# single_coil_driver.net
KiCad netlist of a schematic drawn in Altium Designer
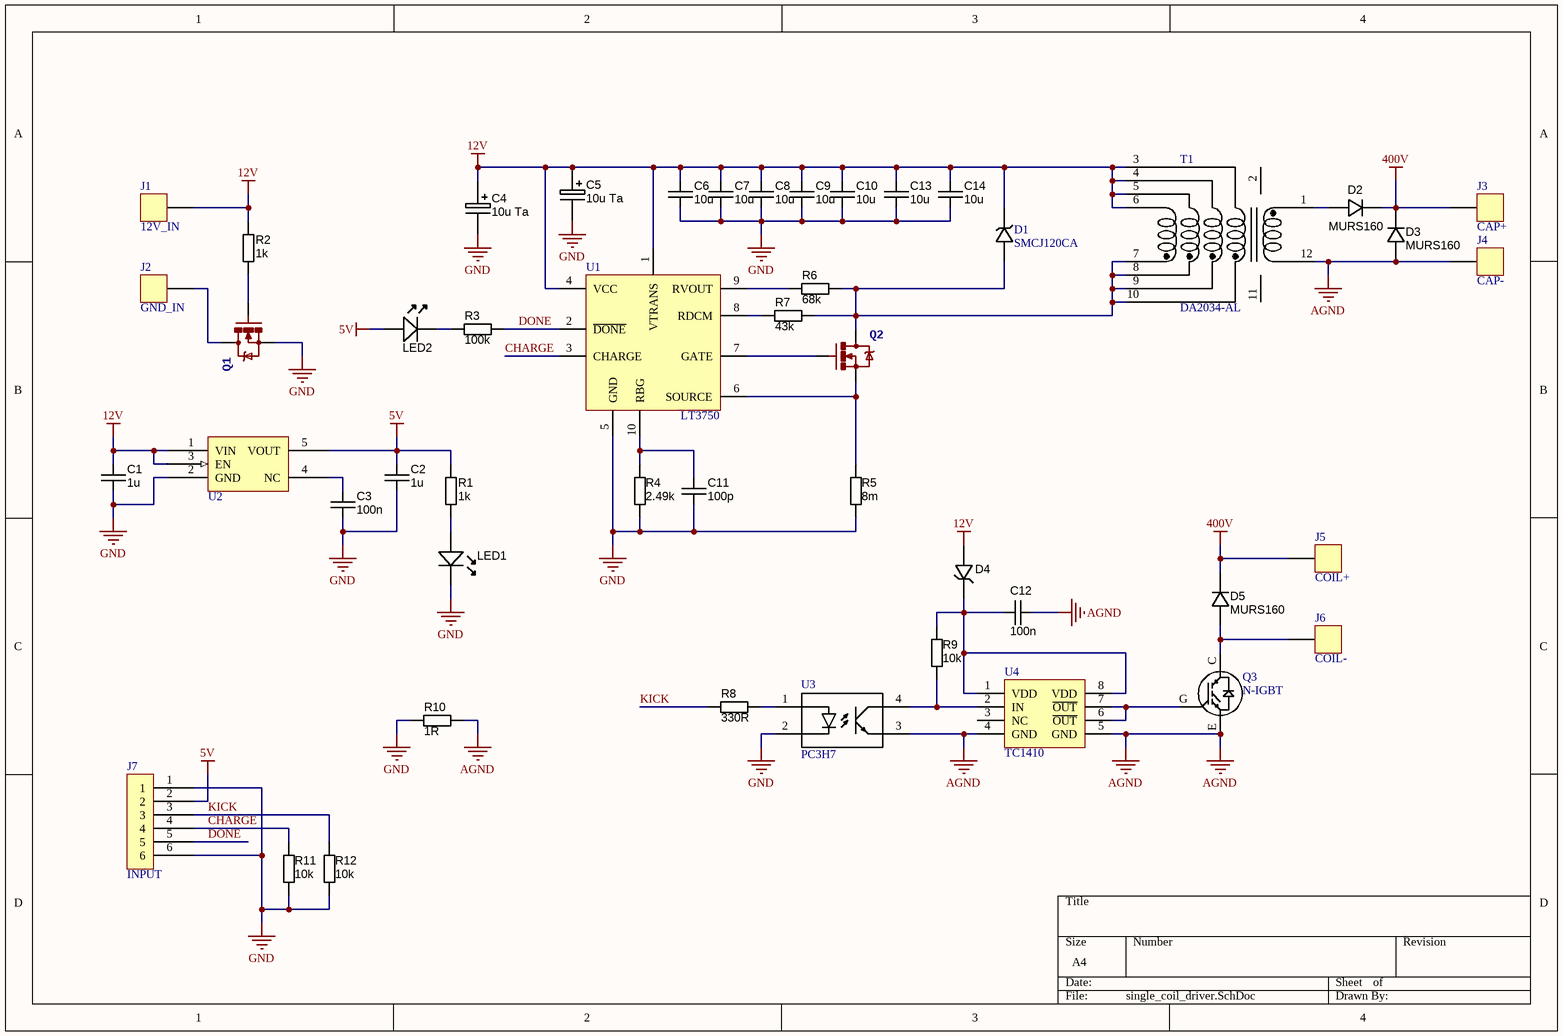
[diagram p0: single_coil_driver.SchDoc]

(export (version "E")
  (design (tool "Eeschema 10.0.6"))
  (components
    (comp (ref "C1")
      (value "1u")
      (footprint "CAPC3216X180N")
      (description "Capacitor SMD Cer 10uF 10% 16V X7R 1206")
      (fields (field (name "TOLERANCE") "±10%"))
      (libsource (lib "PBL - Capacitors") (part "CAPC_10u_1206_16V"))
    )
    (comp (ref "C2")
      (value "1u")
      (footprint "CAPC3216X180N")
      (description "Capacitor SMD Cer 10uF 10% 16V X7R 1206")
      (fields (field (name "TOLERANCE") "±10%"))
      (libsource (lib "PBL - Capacitors") (part "CAPC_10u_1206_16V"))
    )
    (comp (ref "C3")
      (value "100n")
      (footprint "CAPC1608X90N")
      (description "Capacitor SMD Cer 10nF 10% 50V X7R 0603")
      (fields (field (name "TOLERANCE") "±10%"))
      (libsource (lib "PBL - Capacitors") (part "CAPC_10n_0603_X7R_50V_10%"))
    )
    (comp (ref "C4")
      (value "10u Ta")
      (footprint "CAPMP3528X210N")
      (description "Capacitor SMD Tantalum 47uF 20% 6.3V 1210")
      (fields (field (name "TOLERANCE") "±20%"))
      (libsource (lib "PBL - Capacitors") (part "CAPT_47u_1210_6V3"))
    )
    (comp (ref "C5")
      (value "10u Ta")
      (footprint "CAPMP3528X210N")
      (description "Capacitor SMD Tantalum 47uF 20% 6.3V 1210")
      (fields (field (name "TOLERANCE") "±20%"))
      (libsource (lib "PBL - Capacitors") (part "CAPT_47u_1210_6V3"))
    )
    (comp (ref "C6")
      (value "10u")
      (footprint "CAPC3216X180N")
      (description "Capacitor SMD Cer 10uF 10% 16V X7R 1206")
      (fields (field (name "TOLERANCE") "±10%"))
      (libsource (lib "PBL - Capacitors") (part "CAPC_10u_1206_16V"))
    )
    (comp (ref "C7")
      (value "10u")
      (footprint "CAPC3216X180N")
      (description "Capacitor SMD Cer 10uF 10% 16V X7R 1206")
      (fields (field (name "TOLERANCE") "±10%"))
      (libsource (lib "PBL - Capacitors") (part "CAPC_10u_1206_16V"))
    )
    (comp (ref "C8")
      (value "10u")
      (footprint "CAPC3216X180N")
      (description "Capacitor SMD Cer 10uF 10% 16V X7R 1206")
      (fields (field (name "TOLERANCE") "±10%"))
      (libsource (lib "PBL - Capacitors") (part "CAPC_10u_1206_16V"))
    )
    (comp (ref "C9")
      (value "10u")
      (footprint "CAPC3216X180N")
      (description "Capacitor SMD Cer 10uF 10% 16V X7R 1206")
      (fields (field (name "TOLERANCE") "±10%"))
      (libsource (lib "PBL - Capacitors") (part "CAPC_10u_1206_16V"))
    )
    (comp (ref "C10")
      (value "10u")
      (footprint "CAPC3216X180N")
      (description "Capacitor SMD Cer 10uF 10% 16V X7R 1206")
      (fields (field (name "TOLERANCE") "±10%"))
      (libsource (lib "PBL - Capacitors") (part "CAPC_10u_1206_16V"))
    )
    (comp (ref "C11")
      (value "100p")
      (footprint "CAPC1608X90N")
      (description "Capacitor SMD Cer 10nF 10% 50V X7R 0603")
      (fields (field (name "TOLERANCE") "±10%"))
      (libsource (lib "PBL - Capacitors") (part "CAPC_10n_0603_X7R_50V_10%"))
    )
    (comp (ref "C12")
      (value "100n")
      (footprint "CAPC1608X90N")
      (description "Capacitor SMD Cer 10nF 10% 50V X7R 0603")
      (fields (field (name "TOLERANCE") "±10%"))
      (libsource (lib "PBL - Capacitors") (part "CAPC_10n_0603_X7R_50V_10%"))
    )
    (comp (ref "C13")
      (value "10u")
      (footprint "CAPC3216X180N")
      (description "Capacitor SMD Cer 10uF 10% 16V X7R 1206")
      (fields (field (name "TOLERANCE") "±10%"))
      (libsource (lib "PBL - Capacitors") (part "CAPC_10u_1206_16V"))
    )
    (comp (ref "C14")
      (value "10u")
      (footprint "CAPC3216X180N")
      (description "Capacitor SMD Cer 10uF 10% 16V X7R 1206")
      (fields (field (name "TOLERANCE") "±10%"))
      (libsource (lib "PBL - Capacitors") (part "CAPC_10u_1206_16V"))
    )
    (comp (ref "D1")
      (value "SMCJ120CA")
      (footprint "DO-214AB")
      (libsource (lib "coilgun") (part "TVS-DIODE"))
    )
    (comp (ref "D2")
      (value "MURS160")
      (footprint "DO-214AA")
      (description "Diode SMD 100V 1.5A SMA")
      (libsource (lib "PBL - Diodes") (part "DIODE_100V_1.5A_SMA"))
    )
    (comp (ref "D3")
      (value "MURS160")
      (footprint "DO-214AA")
      (description "Diode SMD 100V 1.5A SMA")
      (libsource (lib "PBL - Diodes") (part "DIODE_100V_1.5A_SMA"))
    )
    (comp (ref "D4")
      (value "~")
      (footprint "SOD123")
      (description "Diode Zener SMD 28V 0.5W SOD-123")
      (fields (field (name "TOLERANCE") "±5%"))
      (libsource (lib "PBL - Diodes") (part "DIODE_ZENER_28V_500mW"))
    )
    (comp (ref "D5")
      (value "MURS160")
      (footprint "DO-214AA")
      (description "Diode SMD 100V 1.5A SMA")
      (libsource (lib "PBL - Diodes") (part "DIODE_100V_1.5A_SMA"))
    )
    (comp (ref "J1") (value "12V_IN") (footprint "MEDIUM-POWER-VIA") (libsource (lib "") (part "HEADER-1_1")))
    (comp (ref "J2") (value "GND_IN") (footprint "MEDIUM-POWER-VIA") (libsource (lib "") (part "HEADER-1_1")))
    (comp (ref "J3")
      (value "CAP+")
      (footprint "MEDIUM-POWER-VIA")
      (libsource (lib "connectors") (part "HEADER-1"))
    )
    (comp (ref "J4")
      (value "CAP-")
      (footprint "MEDIUM-POWER-VIA")
      (libsource (lib "connectors") (part "HEADER-1"))
    )
    (comp (ref "J5")
      (value "COIL+")
      (footprint "MEDIUM-POWER-VIA")
      (libsource (lib "connectors") (part "HEADER-1"))
    )
    (comp (ref "J6")
      (value "COIL-")
      (footprint "MEDIUM-POWER-VIA")
      (libsource (lib "connectors") (part "HEADER-1"))
    )
    (comp (ref "J7")
      (value "INPUT")
      (footprint "MICRO-MATCH-6")
      (libsource (lib "connectors") (part "HEADER-6"))
    )
    (comp (ref "LED1")
      (value "Green")
      (footprint "LED-0603-GREEN")
      (description "LED 0603 SMD Green 525nm 350mcd 20mA")
      (libsource (lib "PBL - Light Sources") (part "LED_SMD_Green_0603_525nm_350mcd"))
    )
    (comp (ref "LED2")
      (value "Green")
      (footprint "LED-0603-GREEN")
      (description "LED 0603 SMD Green 525nm 350mcd 20mA")
      (libsource (lib "PBL - Light Sources") (part "LED_SMD_Green_0603_525nm_350mcd"))
    )
    (comp (ref "Q1") (value "MOSFET-N") (footprint "SOT669") (libsource (lib "") (part "MOSFET-N_1")))
    (comp (ref "Q2") (value "MOSFET-N") (footprint "SOT669") (libsource (lib "mosfets") (part "MOSFET-N")))
    (comp (ref "Q3") (value "N-IGBT") (footprint "TO-247") (libsource (lib "coilgun") (part "N-IGBT")))
    (comp (ref "R1")
      (value "1k")
      (footprint "RESC1608X55N")
      (description "Resistor SMD chip 1k Ohm 0.1W 1% 0603")
      (fields (field (name "TOLERANCE") "±1%"))
      (libsource (lib "PBL - Resistors") (part "RES_1K_0603_1%"))
    )
    (comp (ref "R2")
      (value "1k")
      (footprint "RESC1608X55N")
      (description "Resistor SMD chip 1k Ohm 0.1W 1% 0603")
      (fields (field (name "TOLERANCE") "±1%"))
      (libsource (lib "PBL - Resistors") (part "RES_1K_0603_1%"))
    )
    (comp (ref "R3")
      (value "100k")
      (footprint "RESC1608X55N")
      (description "Resistor SMD chip 1k Ohm 0.1W 1% 0603")
      (fields (field (name "TOLERANCE") "±1%"))
      (libsource (lib "") (part "RES_1K_0603_1%_1"))
    )
    (comp (ref "R4")
      (value "2.49k")
      (footprint "RESC1608X55N")
      (description "Resistor SMD chip 1k Ohm 0.1W 1% 0603")
      (fields (field (name "TOLERANCE") "±1%"))
      (libsource (lib "") (part "RES_1K_0603_1%_2"))
    )
    (comp (ref "R5")
      (value "8m")
      (footprint "RESC5025X70N")
      (description "Resistor SMD chip 10 Ohm 0.25W 5% 2010")
      (fields (field (name "TOLERANCE") "±5%"))
      (libsource (lib "PBL - Resistors") (part "RES_10R_2010_5%"))
    )
    (comp (ref "R6")
      (value "68k")
      (footprint "RESC1608X55N")
      (description "Resistor SMD chip 1k Ohm 0.1W 1% 0603")
      (fields (field (name "TOLERANCE") "±1%"))
      (libsource (lib "") (part "RES_1K_0603_1%_3"))
    )
    (comp (ref "R7")
      (value "43k")
      (footprint "RESC1608X55N")
      (description "Resistor SMD chip 1k Ohm 0.1W 1% 0603")
      (fields (field (name "TOLERANCE") "±1%"))
      (libsource (lib "") (part "RES_1K_0603_1%_3"))
    )
    (comp (ref "R8")
      (value "330R")
      (footprint "RESC1608X55N")
      (description "Resistor SMD chip 1k Ohm 0.1W 1% 0603")
      (fields (field (name "TOLERANCE") "±1%"))
      (libsource (lib "") (part "RES_1K_0603_1%_1"))
    )
    (comp (ref "R9")
      (value "10k")
      (footprint "RESC1608X55N")
      (description "Resistor SMD chip 1k Ohm 0.1W 1% 0603")
      (fields (field (name "TOLERANCE") "±1%"))
      (libsource (lib "PBL - Resistors") (part "RES_1K_0603_1%"))
    )
    (comp (ref "R10")
      (value "1R")
      (footprint "RESC1608X55N")
      (description "Resistor SMD chip 1k Ohm 0.1W 1% 0603")
      (fields (field (name "TOLERANCE") "±1%"))
      (libsource (lib "") (part "RES_1K_0603_1%_1"))
    )
    (comp (ref "R11")
      (value "10k")
      (footprint "RESC1608X55N")
      (description "Resistor SMD chip 1k Ohm 0.1W 1% 0603")
      (fields (field (name "TOLERANCE") "±1%"))
      (libsource (lib "PBL - Resistors") (part "RES_1K_0603_1%"))
    )
    (comp (ref "R12")
      (value "10k")
      (footprint "RESC1608X55N")
      (description "Resistor SMD chip 1k Ohm 0.1W 1% 0603")
      (fields (field (name "TOLERANCE") "±1%"))
      (libsource (lib "PBL - Resistors") (part "RES_1K_0603_1%"))
    )
    (comp (ref "T1")
      (value "DA2034-AL")
      (footprint "DA2034-AL")
      (libsource (lib "coilgun") (part "DA2034-AL"))
    )
    (comp (ref "U1") (value "LT3750") (footprint "MSOP-10") (libsource (lib "coilgun") (part "LT3750")))
    (comp (ref "U2")
      (value "LDO-SOT23-5")
      (footprint "SOT23-5")
      (libsource (lib "power") (part "LDO-SOT23-5"))
    )
    (comp (ref "U3")
      (value "PC3H7")
      (footprint "SOIC127P680X230-4M")
      (libsource (lib "coilgun") (part "PC3H7"))
    )
    (comp (ref "U4") (value "TC1410") (footprint "SO8") (libsource (lib "coilgun") (part "TC1410")))
  )
  (nets
    (net (code "1") (name "/CHARGE") (class "Default")
      (node (ref "J7") (pin "4") (pinfunction "4_4") (pintype "passive"))
      (node (ref "R11") (pin "1") (pinfunction "1_1") (pintype "passive"))
      (node (ref "U1") (pin "3") (pinfunction "CHARGE_3") (pintype "passive"))
    )
    (net (code "2") (name "/DONE") (class "Default")
      (node (ref "J7") (pin "5") (pinfunction "5_5") (pintype "passive"))
      (node (ref "R3") (pin "1") (pinfunction "1_1") (pintype "passive"))
      (node (ref "U1") (pin "2") (pinfunction "~{DONE}_2") (pintype "passive"))
    )
    (net (code "3") (name "/KICK") (class "Default")
      (node (ref "J7") (pin "3") (pinfunction "3_3") (pintype "passive"))
      (node (ref "R12") (pin "1") (pinfunction "1_1") (pintype "passive"))
      (node (ref "R8") (pin "2") (pinfunction "2_2") (pintype "passive"))
    )
    (net (code "4") (name "5V") (class "Default")
      (node (ref "C2") (pin "1") (pintype "passive"))
      (node (ref "J7") (pin "2") (pinfunction "2_2") (pintype "passive"))
      (node (ref "LED2") (pin "A") (pinfunction "A_A") (pintype "passive"))
      (node (ref "R1") (pin "1") (pinfunction "1_1") (pintype "passive"))
      (node (ref "U2") (pin "5") (pinfunction "VOUT_5") (pintype "passive"))
    )
    (net (code "5") (name "12V") (class "Default")
      (node (ref "C1") (pin "1") (pintype "passive"))
      (node (ref "C10") (pin "1") (pintype "passive"))
      (node (ref "C13") (pin "1") (pintype "passive"))
      (node (ref "C14") (pin "1") (pintype "passive"))
      (node (ref "C4") (pin "1") (pintype "passive"))
      (node (ref "C5") (pin "1") (pintype "passive"))
      (node (ref "C6") (pin "1") (pintype "passive"))
      (node (ref "C7") (pin "1") (pintype "passive"))
      (node (ref "C8") (pin "1") (pintype "passive"))
      (node (ref "C9") (pin "1") (pintype "passive"))
      (node (ref "D1") (pin "1") (pinfunction "1_1") (pintype "passive"))
      (node (ref "D4") (pin "A") (pinfunction "A_A") (pintype "passive"))
      (node (ref "J1") (pin "1") (pinfunction "1_1") (pintype "passive"))
      (node (ref "R2") (pin "1") (pinfunction "1_1") (pintype "passive"))
      (node (ref "T1") (pin "3") (pinfunction "3_3") (pintype "passive"))
      (node (ref "T1") (pin "4") (pinfunction "4_4") (pintype "passive"))
      (node (ref "T1") (pin "5") (pinfunction "5_5") (pintype "passive"))
      (node (ref "T1") (pin "6") (pinfunction "6_6") (pintype "passive"))
      (node (ref "U1") (pin "1") (pinfunction "VTRANS_1") (pintype "passive"))
      (node (ref "U1") (pin "4") (pinfunction "VCC_4") (pintype "passive"))
      (node (ref "U2") (pin "1") (pinfunction "VIN_1") (pintype "power_in"))
      (node (ref "U2") (pin "3") (pinfunction "EN_3") (pintype "input"))
    )
    (net (code "6") (name "400V") (class "Default")
      (node (ref "D2") (pin "K") (pinfunction "K_K") (pintype "passive"))
      (node (ref "D3") (pin "K") (pinfunction "K_K") (pintype "passive"))
      (node (ref "D5") (pin "K") (pinfunction "K_K") (pintype "passive"))
      (node (ref "J3") (pin "1") (pinfunction "1_1") (pintype "passive"))
      (node (ref "J5") (pin "1") (pinfunction "1_1") (pintype "passive"))
    )
    (net (code "7") (name "AGND") (class "Default")
      (node (ref "C12") (pin "2") (pintype "passive"))
      (node (ref "D3") (pin "A") (pinfunction "A_A") (pintype "passive"))
      (node (ref "J4") (pin "1") (pinfunction "1_1") (pintype "passive"))
      (node (ref "Q3") (pin "E") (pinfunction "E_E") (pintype "passive"))
      (node (ref "R10") (pin "1") (pinfunction "1_1") (pintype "passive"))
      (node (ref "T1") (pin "12") (pinfunction "12_12") (pintype "passive"))
      (node (ref "U3") (pin "3") (pinfunction "3_3") (pintype "passive"))
      (node (ref "U4") (pin "4") (pinfunction "GND_4") (pintype "passive"))
      (node (ref "U4") (pin "5") (pinfunction "GND_5") (pintype "passive"))
    )
    (net (code "8") (name "GND") (class "Default")
      (node (ref "C1") (pin "2") (pintype "passive"))
      (node (ref "C10") (pin "2") (pintype "passive"))
      (node (ref "C11") (pin "2") (pintype "passive"))
      (node (ref "C13") (pin "2") (pintype "passive"))
      (node (ref "C14") (pin "2") (pintype "passive"))
      (node (ref "C2") (pin "2") (pintype "passive"))
      (node (ref "C3") (pin "2") (pintype "passive"))
      (node (ref "C4") (pin "2") (pintype "passive"))
      (node (ref "C5") (pin "2") (pintype "passive"))
      (node (ref "C6") (pin "2") (pintype "passive"))
      (node (ref "C7") (pin "2") (pintype "passive"))
      (node (ref "C8") (pin "2") (pintype "passive"))
      (node (ref "C9") (pin "2") (pintype "passive"))
      (node (ref "J7") (pin "1") (pinfunction "1_1") (pintype "passive"))
      (node (ref "J7") (pin "6") (pinfunction "6_6") (pintype "passive"))
      (node (ref "LED1") (pin "K") (pinfunction "K_K") (pintype "passive"))
      (node (ref "Q1") (pin "S") (pinfunction "S_S") (pintype "passive"))
      (node (ref "R10") (pin "2") (pinfunction "2_2") (pintype "passive"))
      (node (ref "R11") (pin "2") (pinfunction "2_2") (pintype "passive"))
      (node (ref "R12") (pin "2") (pinfunction "2_2") (pintype "passive"))
      (node (ref "R4") (pin "1") (pinfunction "1_1") (pintype "passive"))
      (node (ref "R5") (pin "2") (pinfunction "2_2") (pintype "passive"))
      (node (ref "U1") (pin "5") (pinfunction "GND_5") (pintype "passive"))
      (node (ref "U2") (pin "2") (pinfunction "GND_2") (pintype "power_in"))
      (node (ref "U3") (pin "2") (pinfunction "2_2") (pintype "passive"))
    )
    (net (code "9") (name "Net-(C12-Pad1)") (class "Default")
      (node (ref "C12") (pin "1") (pintype "passive"))
      (node (ref "D4") (pin "K") (pinfunction "K_K") (pintype "passive"))
      (node (ref "R9") (pin "1") (pinfunction "1_1") (pintype "passive"))
      (node (ref "U4") (pin "1") (pinfunction "VDD_1") (pintype "passive"))
      (node (ref "U4") (pin "8") (pinfunction "VDD_8") (pintype "passive"))
    )
    (net (code "10") (name "Net-(D1-Pad2)") (class "Default")
      (node (ref "D1") (pin "2") (pinfunction "2_2") (pintype "passive"))
      (node (ref "Q2") (pin "D") (pinfunction "D_D") (pintype "passive"))
      (node (ref "R6") (pin "2") (pinfunction "2_2") (pintype "passive"))
      (node (ref "R7") (pin "2") (pinfunction "2_2") (pintype "passive"))
      (node (ref "T1") (pin "10") (pinfunction "10_10") (pintype "passive"))
      (node (ref "T1") (pin "7") (pinfunction "7_7") (pintype "passive"))
      (node (ref "T1") (pin "8") (pinfunction "8_8") (pintype "passive"))
      (node (ref "T1") (pin "9") (pinfunction "9_9") (pintype "passive"))
    )
    (net (code "11") (name "Net-(D2-PadA)") (class "Default")
      (node (ref "D2") (pin "A") (pinfunction "A_A") (pintype "passive"))
      (node (ref "T1") (pin "1") (pinfunction "1_1") (pintype "passive"))
    )
    (net (code "12") (name "Net-(D5-PadA)") (class "Default")
      (node (ref "D5") (pin "A") (pinfunction "A_A") (pintype "passive"))
      (node (ref "J6") (pin "1") (pinfunction "1_1") (pintype "passive"))
      (node (ref "Q3") (pin "C") (pinfunction "C_C") (pintype "passive"))
    )
    (net (code "13") (name "Net-(J2-Pad1)") (class "Default")
      (node (ref "J2") (pin "1") (pinfunction "1_1") (pintype "passive"))
      (node (ref "Q1") (pin "D") (pinfunction "D_D") (pintype "passive"))
    )
    (net (code "14") (name "Net-(LED1-PadA)") (class "Default")
      (node (ref "LED1") (pin "A") (pinfunction "A_A") (pintype "passive"))
      (node (ref "R1") (pin "2") (pinfunction "2_2") (pintype "passive"))
    )
    (net (code "15") (name "Net-(LED2-PadK)") (class "Default")
      (node (ref "LED2") (pin "K") (pinfunction "K_K") (pintype "passive"))
      (node (ref "R3") (pin "2") (pinfunction "2_2") (pintype "passive"))
    )
    (net (code "16") (name "Net-(Q1-PadG)") (class "Default")
      (node (ref "Q1") (pin "G") (pinfunction "G_G") (pintype "passive"))
      (node (ref "R2") (pin "2") (pinfunction "2_2") (pintype "passive"))
    )
    (net (code "17") (name "Net-(Q3-PadG)") (class "Default")
      (node (ref "Q3") (pin "G") (pinfunction "G_G") (pintype "passive"))
      (node (ref "U4") (pin "6") (pinfunction "~{OUT}_6") (pintype "passive"))
      (node (ref "U4") (pin "7") (pinfunction "~{OUT}_7") (pintype "passive"))
    )
    (net (code "18") (name "Net-(R8-Pad1)") (class "Default")
      (node (ref "R8") (pin "1") (pinfunction "1_1") (pintype "passive"))
      (node (ref "U3") (pin "1") (pinfunction "1_1") (pintype "passive"))
    )
    (net (code "19") (name "Net-(U1-GATE)") (class "Default")
      (node (ref "Q2") (pin "G") (pinfunction "G_G") (pintype "passive"))
      (node (ref "U1") (pin "7") (pinfunction "GATE_7") (pintype "passive"))
    )
    (net (code "20") (name "Net-(U1-RBG)") (class "Default")
      (node (ref "C11") (pin "1") (pintype "passive"))
      (node (ref "R4") (pin "2") (pinfunction "2_2") (pintype "passive"))
      (node (ref "U1") (pin "10") (pinfunction "RBG_10") (pintype "passive"))
    )
    (net (code "21") (name "Net-(U1-RDCM)") (class "Default")
      (node (ref "R7") (pin "1") (pinfunction "1_1") (pintype "passive"))
      (node (ref "U1") (pin "8") (pinfunction "RDCM_8") (pintype "passive"))
    )
    (net (code "22") (name "Net-(U1-RVOUT)") (class "Default")
      (node (ref "R6") (pin "1") (pinfunction "1_1") (pintype "passive"))
      (node (ref "U1") (pin "9") (pinfunction "RVOUT_9") (pintype "passive"))
    )
    (net (code "23") (name "Net-(U1-SOURCE)") (class "Default")
      (node (ref "Q2") (pin "S") (pinfunction "S_S") (pintype "passive"))
      (node (ref "R5") (pin "1") (pinfunction "1_1") (pintype "passive"))
      (node (ref "U1") (pin "6") (pinfunction "SOURCE_6") (pintype "passive"))
    )
    (net (code "24") (name "Net-(U2-NC)") (class "Default")
      (node (ref "C3") (pin "1") (pintype "passive"))
      (node (ref "U2") (pin "4") (pinfunction "NC_4") (pintype "power_in"))
    )
    (net (code "25") (name "Net-(U4-IN)") (class "Default")
      (node (ref "R9") (pin "2") (pinfunction "2_2") (pintype "passive"))
      (node (ref "U3") (pin "4") (pinfunction "4_4") (pintype "passive"))
      (node (ref "U4") (pin "2") (pinfunction "IN_2") (pintype "passive"))
    )
    (net (code "26") (name "unconnected-(T1-Pad2)") (class "Default")
      (node (ref "T1") (pin "2") (pinfunction "2_2") (pintype "passive"))
    )
    (net (code "27") (name "unconnected-(T1-Pad11)") (class "Default")
      (node (ref "T1") (pin "11") (pinfunction "11_11") (pintype "passive"))
    )
    (net (code "28") (name "unconnected-(U4-NC-Pad3)") (class "Default")
      (node (ref "U4") (pin "3") (pinfunction "NC_3") (pintype "passive"))
    )
  )
)
